# mikrophonie_2_r2.net
KiCad netlist of a schematic drawn in EAGLE
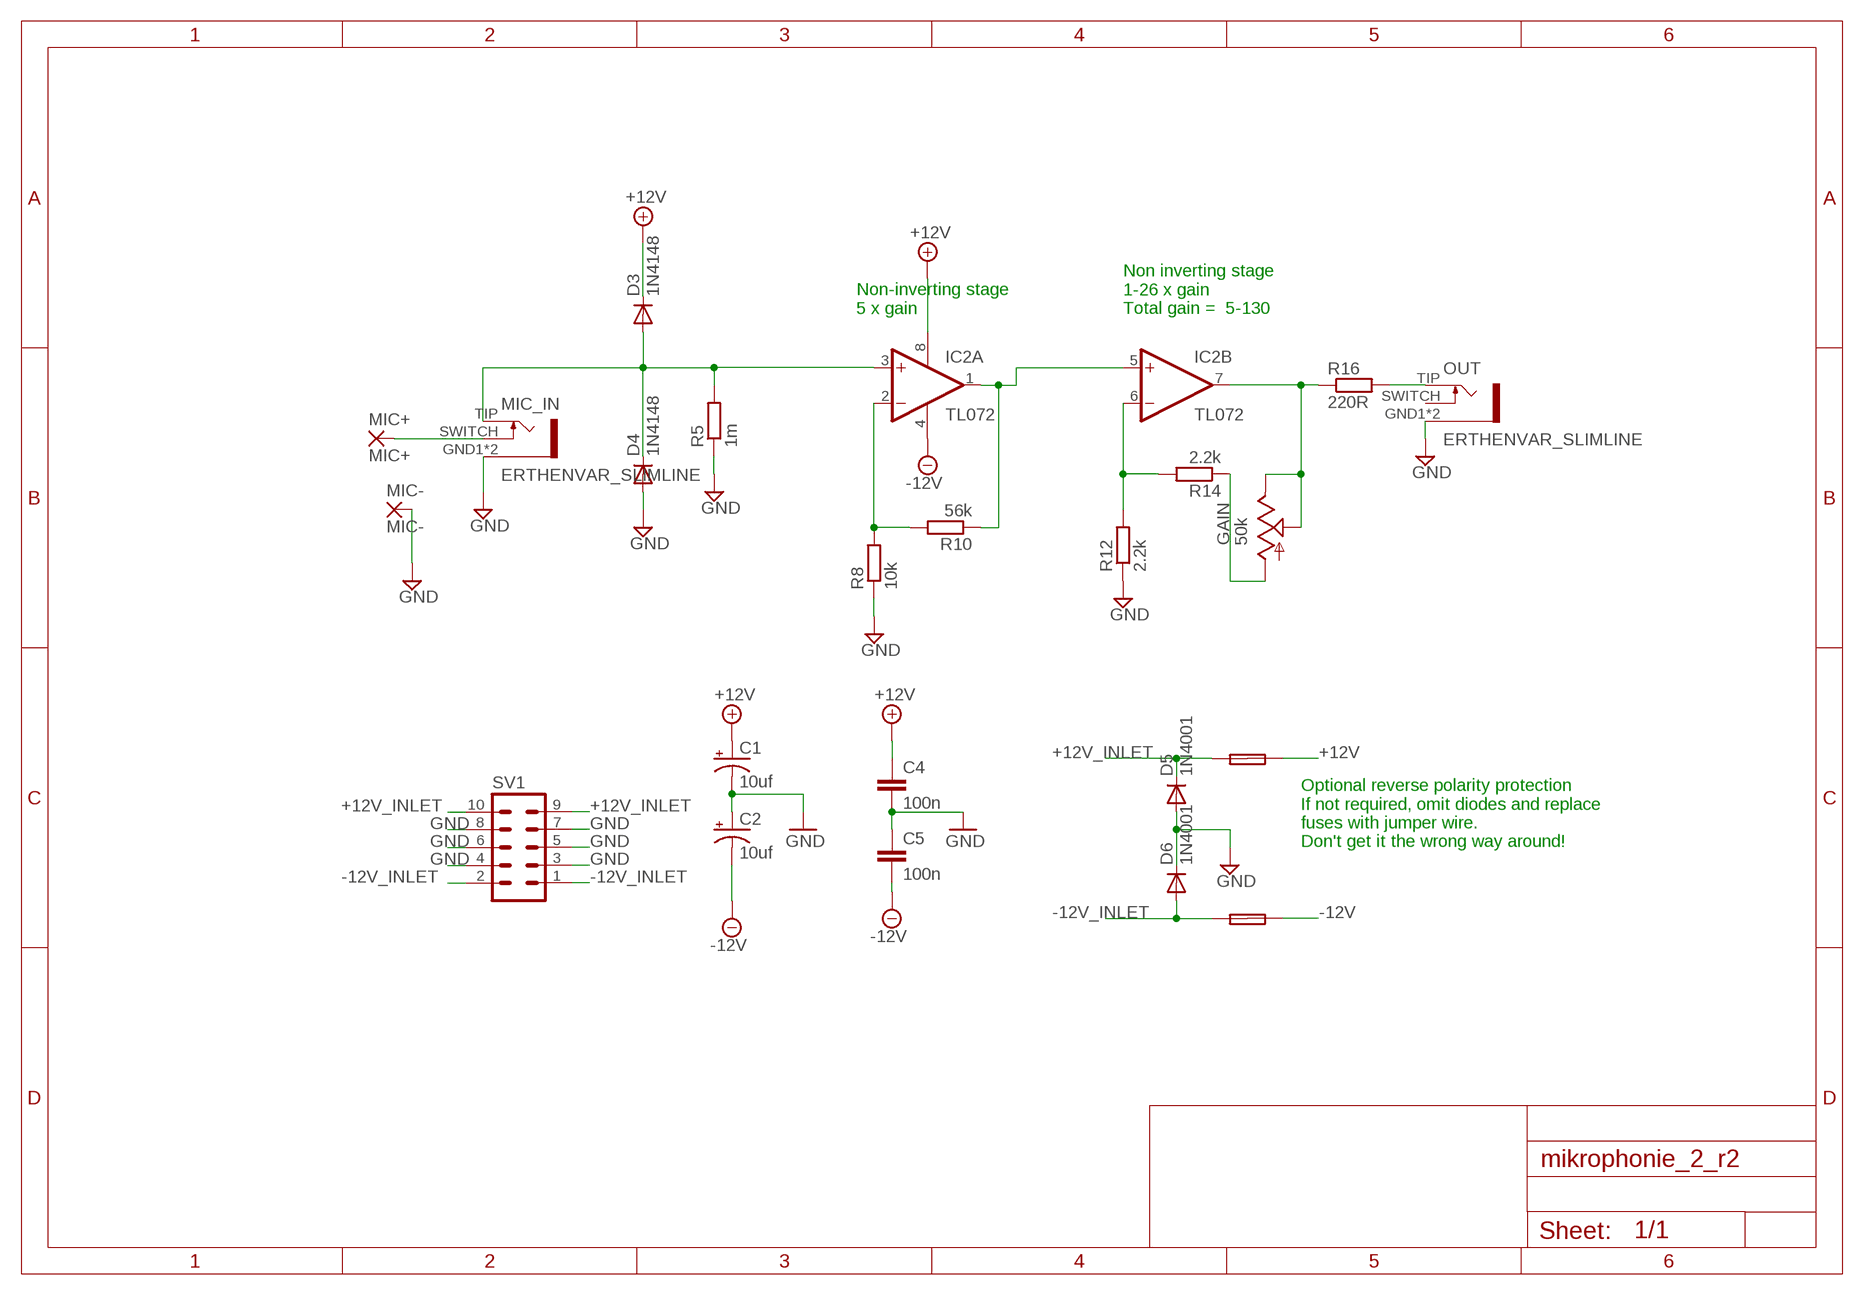
[diagram p0: schematic, sheet 1]

(export (version "E")
  (design (tool "Eeschema 10.0.6"))
  (components
    (comp (ref "1")
      (value "FUSE")
      (footprint "eagle-import:C050H075X075")
      (libsource (lib "eagle-import") (part "PTC_FUSEPOLY_FUSE"))
    )
    (comp (ref "C1")
      (value "10uf")
      (footprint "eagle-import:CPOL-RADIAL-10UF-25V")
      (libsource (lib "eagle-import") (part "CAP_POLPTH2"))
    )
    (comp (ref "C2")
      (value "10uf")
      (footprint "eagle-import:CPOL-RADIAL-10UF-25V")
      (libsource (lib "eagle-import") (part "CAP_POLPTH2"))
    )
    (comp (ref "C4")
      (value "100n")
      (footprint "eagle-import:C050-024X044")
      (libsource (lib "eagle-import") (part "C-EU050-024X044"))
    )
    (comp (ref "C5")
      (value "100n")
      (footprint "eagle-import:C050-024X044")
      (libsource (lib "eagle-import") (part "C-EU050-024X044"))
    )
    (comp (ref "D3")
      (value "1N4148")
      (footprint "eagle-import:DO35-7")
      (libsource (lib "eagle-import") (part "1N4148DO35-7"))
    )
    (comp (ref "D4")
      (value "1N4148")
      (footprint "eagle-import:DO35-7")
      (libsource (lib "eagle-import") (part "diode_1N4148DO35-7"))
    )
    (comp (ref "D5")
      (value "1N4001")
      (footprint "eagle-import:DO41-10")
      (libsource (lib "eagle-import") (part "1N4004"))
    )
    (comp (ref "D6")
      (value "1N4001")
      (footprint "eagle-import:DO41-10")
      (libsource (lib "eagle-import") (part "1N4004"))
    )
    (comp (ref "FUSE")
      (value "FUSE")
      (footprint "eagle-import:C050H075X075")
      (libsource (lib "eagle-import") (part "PTC_FUSEPOLY_FUSE"))
    )
    (comp (ref "GAIN")
      (value "50k")
      (footprint "eagle-import:EVUF")
      (libsource (lib "eagle-import") (part "ALPHA-9MMAF2"))
    )
    (comp (ref "IC2")
      (value "TL072")
      (footprint "eagle-import:DIL08")
      (libsource (lib "eagle-import") (part "TL072P"))
    )
    (comp (ref "MIC+")
      (value "MIC+")
      (footprint "eagle-import:LONG_PAD_1")
      (libsource (lib "eagle-import") (part "LONG_PAD_1"))
    )
    (comp (ref "MIC-")
      (value "MIC-")
      (footprint "eagle-import:LONG_PAD_1")
      (libsource (lib "eagle-import") (part "LONG_PAD_1"))
    )
    (comp (ref "MIC_IN")
      (value "ERTHENVAR_SLIMLINE")
      (footprint "eagle-import:ERTHENVAR_SLIMLINE")
      (libsource (lib "eagle-import") (part "ERTHENVAR_SLIMLINE"))
    )
    (comp (ref "OUT")
      (value "ERTHENVAR_SLIMLINE")
      (footprint "eagle-import:ERTHENVAR_SLIMLINE")
      (libsource (lib "eagle-import") (part "ERTHENVAR_SLIMLINE"))
    )
    (comp (ref "R5")
      (value "1m")
      (footprint "eagle-import:0207_10")
      (libsource (lib "eagle-import") (part "R-EU_STANDARD_RESISTOR"))
    )
    (comp (ref "R8")
      (value "10k")
      (footprint "eagle-import:0207_10")
      (libsource (lib "eagle-import") (part "R-EU_STANDARD_RESISTOR"))
    )
    (comp (ref "R10")
      (value "56k")
      (footprint "eagle-import:0207_10")
      (libsource (lib "eagle-import") (part "R-EU_STANDARD_RESISTOR"))
    )
    (comp (ref "R12")
      (value "2.2k")
      (footprint "eagle-import:0207_10")
      (libsource (lib "eagle-import") (part "R-EU_STANDARD_RESISTOR"))
    )
    (comp (ref "R14")
      (value "2.2k")
      (footprint "eagle-import:0207_10")
      (libsource (lib "eagle-import") (part "R-EU_STANDARD_RESISTOR"))
    )
    (comp (ref "R16")
      (value "220R")
      (footprint "eagle-import:0207_10")
      (libsource (lib "eagle-import") (part "R-EU_STANDARD_RESISTOR"))
    )
    (comp (ref "SV1")
      (value "10_PIN_HEADER")
      (footprint "eagle-import:MA05-2")
      (libsource (lib "eagle-import") (part "10_PIN_HEADER"))
    )
  )
  (nets
    (net (code "1") (name "+12V") (class "Default")
      (node (ref "1") (pin "2") (pinfunction "P$2_2") (pintype "bidirectional"))
      (node (ref "C1") (pin "1") (pinfunction "+_1") (pintype "passive"))
      (node (ref "C4") (pin "1") (pinfunction "1_1") (pintype "passive"))
      (node (ref "D3") (pin "C") (pinfunction "C_C") (pintype "passive"))
      (node (ref "IC2") (pin "8") (pinfunction "V+_8") (pintype "power_in"))
    )
    (net (code "2") (name "-12V") (class "Default")
      (node (ref "C2") (pin "2") (pinfunction "-_2") (pintype "passive"))
      (node (ref "C5") (pin "2") (pinfunction "2_2") (pintype "passive"))
      (node (ref "FUSE") (pin "2") (pinfunction "P$2_2") (pintype "bidirectional"))
      (node (ref "IC2") (pin "4") (pinfunction "V-_4") (pintype "power_in"))
    )
    (net (code "3") (name "/+12V_INLET") (class "Default")
      (node (ref "1") (pin "1") (pinfunction "P$1_1") (pintype "bidirectional"))
      (node (ref "D5") (pin "C") (pinfunction "C_C") (pintype "passive"))
      (node (ref "SV1") (pin "10") (pinfunction "10_10") (pintype "passive"))
      (node (ref "SV1") (pin "9") (pinfunction "9_9") (pintype "passive"))
    )
    (net (code "4") (name "/-12V_INLET") (class "Default")
      (node (ref "D6") (pin "A") (pinfunction "A_A") (pintype "passive"))
      (node (ref "FUSE") (pin "1") (pinfunction "P$1_1") (pintype "bidirectional"))
      (node (ref "SV1") (pin "1") (pinfunction "1_1") (pintype "passive"))
      (node (ref "SV1") (pin "2") (pinfunction "2_2") (pintype "passive"))
    )
    (net (code "5") (name "GND") (class "Default")
      (node (ref "C1") (pin "2") (pinfunction "-_2") (pintype "passive"))
      (node (ref "C2") (pin "1") (pinfunction "+_1") (pintype "passive"))
      (node (ref "C4") (pin "2") (pinfunction "2_2") (pintype "passive"))
      (node (ref "C5") (pin "1") (pinfunction "1_1") (pintype "passive"))
      (node (ref "D4") (pin "A") (pinfunction "A_A") (pintype "passive"))
      (node (ref "D5") (pin "A") (pinfunction "A_A") (pintype "passive"))
      (node (ref "D6") (pin "C") (pinfunction "C_C") (pintype "passive"))
      (node (ref "MIC-") (pin "P$1") (pinfunction "P_P$1") (pintype "passive"))
      (node (ref "MIC_IN") (pin "GND1") (pinfunction "5_GND1") (pintype "passive"))
      (node (ref "MIC_IN") (pin "GND2") (pinfunction "5_GND2") (pintype "passive"))
      (node (ref "OUT") (pin "GND1") (pinfunction "5_GND1") (pintype "passive"))
      (node (ref "OUT") (pin "GND2") (pinfunction "5_GND2") (pintype "passive"))
      (node (ref "R12") (pin "1") (pinfunction "1_1") (pintype "passive"))
      (node (ref "R5") (pin "1") (pinfunction "1_1") (pintype "passive"))
      (node (ref "R8") (pin "1") (pinfunction "1_1") (pintype "passive"))
      (node (ref "SV1") (pin "3") (pinfunction "3_3") (pintype "passive"))
      (node (ref "SV1") (pin "4") (pinfunction "4_4") (pintype "passive"))
      (node (ref "SV1") (pin "5") (pinfunction "5_5") (pintype "passive"))
      (node (ref "SV1") (pin "6") (pinfunction "6_6") (pintype "passive"))
      (node (ref "SV1") (pin "7") (pinfunction "7_7") (pintype "passive"))
      (node (ref "SV1") (pin "8") (pinfunction "8_8") (pintype "passive"))
    )
    (net (code "6") (name "Net-(GAIN-A)") (class "Default")
      (node (ref "GAIN") (pin "1") (pinfunction "A_1") (pintype "passive"))
      (node (ref "R14") (pin "1") (pinfunction "1_1") (pintype "passive"))
    )
    (net (code "7") (name "Net-(GAIN-E)") (class "Default")
      (node (ref "GAIN") (pin "2") (pinfunction "S_2") (pintype "passive"))
      (node (ref "GAIN") (pin "3") (pinfunction "E_3") (pintype "passive"))
      (node (ref "IC2") (pin "7") (pinfunction "OUT_7") (pintype "output"))
      (node (ref "R16") (pin "1") (pinfunction "1_1") (pintype "passive"))
    )
    (net (code "8") (name "Net-(IC2A-+IN)") (class "Default")
      (node (ref "D3") (pin "A") (pinfunction "A_A") (pintype "passive"))
      (node (ref "D4") (pin "C") (pinfunction "C_C") (pintype "passive"))
      (node (ref "IC2") (pin "3") (pinfunction "+IN_3") (pintype "input"))
      (node (ref "MIC_IN") (pin "TIP") (pinfunction "3_TIP") (pintype "passive"))
      (node (ref "R5") (pin "2") (pinfunction "2_2") (pintype "passive"))
    )
    (net (code "9") (name "Net-(IC2A--IN)") (class "Default")
      (node (ref "IC2") (pin "2") (pinfunction "-IN_2") (pintype "input"))
      (node (ref "R10") (pin "2") (pinfunction "2_2") (pintype "passive"))
      (node (ref "R8") (pin "2") (pinfunction "2_2") (pintype "passive"))
    )
    (net (code "10") (name "Net-(IC2A-OUT)") (class "Default")
      (node (ref "IC2") (pin "1") (pinfunction "OUT_1") (pintype "output"))
      (node (ref "IC2") (pin "5") (pinfunction "+IN_5") (pintype "input"))
      (node (ref "R10") (pin "1") (pinfunction "1_1") (pintype "passive"))
    )
    (net (code "11") (name "Net-(IC2B--IN)") (class "Default")
      (node (ref "IC2") (pin "6") (pinfunction "-IN_6") (pintype "input"))
      (node (ref "R12") (pin "2") (pinfunction "2_2") (pintype "passive"))
      (node (ref "R14") (pin "2") (pinfunction "2_2") (pintype "passive"))
    )
    (net (code "12") (name "Net-(MIC+-P)") (class "Default")
      (node (ref "MIC+") (pin "P$1") (pinfunction "P_P$1") (pintype "passive"))
      (node (ref "MIC_IN") (pin "SWITCH") (pinfunction "4_SWITCH") (pintype "passive"))
    )
    (net (code "13") (name "Net-(OUT-3)") (class "Default")
      (node (ref "OUT") (pin "TIP") (pinfunction "3_TIP") (pintype "passive"))
      (node (ref "R16") (pin "2") (pinfunction "2_2") (pintype "passive"))
    )
    (net (code "14") (name "unconnected-(OUT-4-PadSWITCH)") (class "Default")
      (node (ref "OUT") (pin "SWITCH") (pinfunction "4_SWITCH") (pintype "passive"))
    )
  )
)
